# SonarandLEDBoard.net
KiCad netlist of a schematic drawn in EAGLE
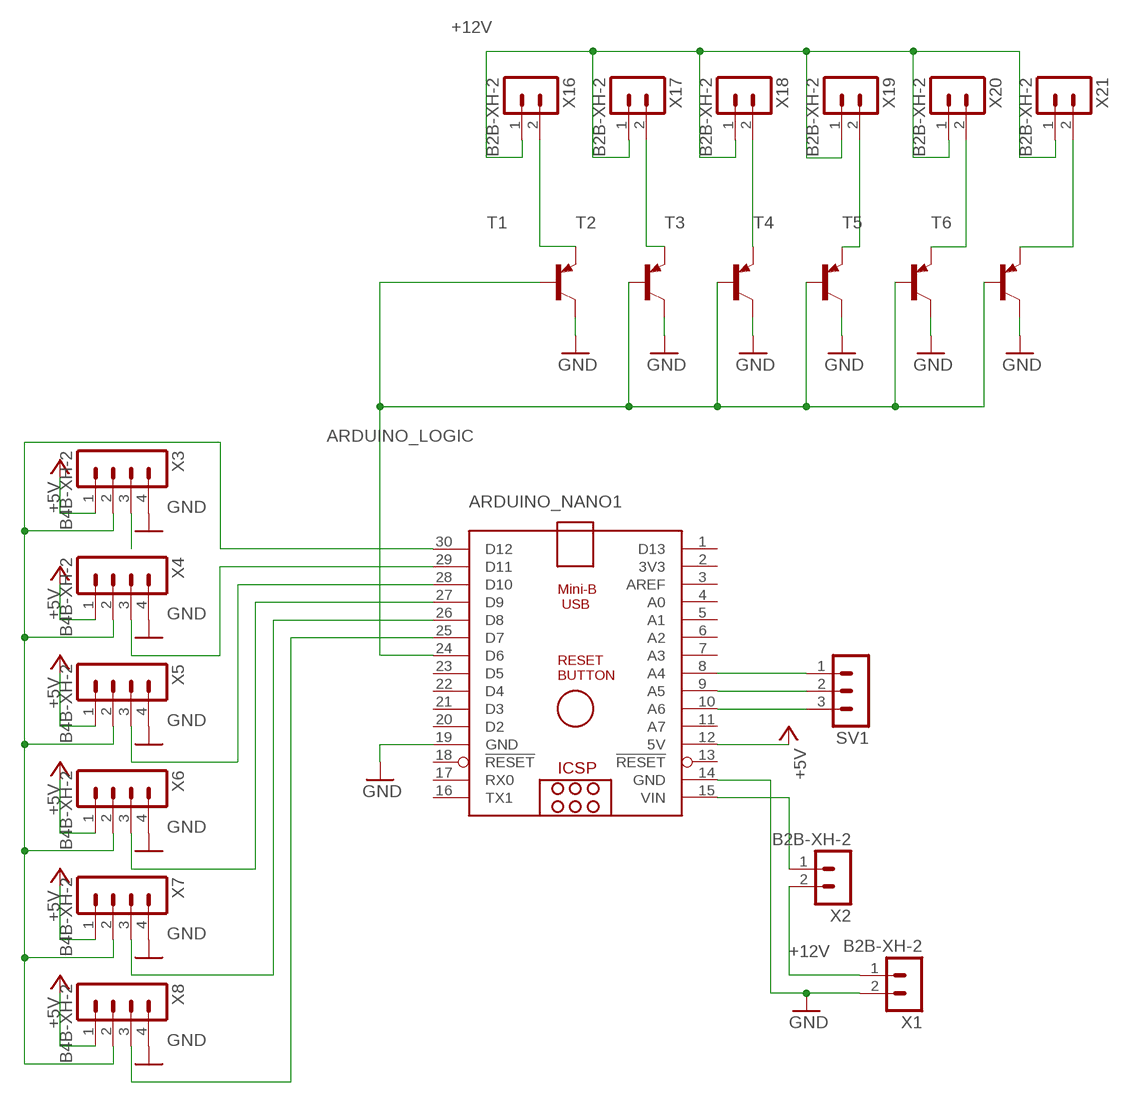
[diagram p0: schematic, sheet 1]

(export (version "E")
  (design (tool "Eeschema 10.0.6"))
  (components
    (comp (ref "ARDUINO_NANO1")
      (value "ARDUINO_NANO")
      (footprint "eagle-import:ARDUINO_NANO")
      (libsource (lib "eagle-import") (part "ARDUINO_NANO"))
    )
    (comp (ref "SV1")
      (value "MA03-1")
      (footprint "eagle-import:MA03-1")
      (libsource (lib "eagle-import") (part "MA03-1"))
    )
    (comp (ref "T1")
      (value "-PNP-TOP3V")
      (footprint "eagle-import:TOP3V")
      (libsource (lib "eagle-import") (part "-PNP-TOP3V"))
    )
    (comp (ref "T2")
      (value "-PNP-TOP3V")
      (footprint "eagle-import:TOP3V")
      (libsource (lib "eagle-import") (part "-PNP-TOP3V"))
    )
    (comp (ref "T3")
      (value "-PNP-TOP3V")
      (footprint "eagle-import:TOP3V")
      (libsource (lib "eagle-import") (part "-PNP-TOP3V"))
    )
    (comp (ref "T4")
      (value "-PNP-TOP3V")
      (footprint "eagle-import:TOP3V")
      (libsource (lib "eagle-import") (part "-PNP-TOP3V"))
    )
    (comp (ref "T5")
      (value "-PNP-TOP3V")
      (footprint "eagle-import:TOP3V")
      (libsource (lib "eagle-import") (part "-PNP-TOP3V"))
    )
    (comp (ref "T6")
      (value "-PNP-TOP3V")
      (footprint "eagle-import:TOP3V")
      (libsource (lib "eagle-import") (part "-PNP-TOP3V"))
    )
    (comp (ref "X1")
      (value "B2B-XH-2")
      (footprint "eagle-import:B2B-XH-A")
      (libsource (lib "eagle-import") (part "B2B-XH-2"))
    )
    (comp (ref "X2")
      (value "B2B-XH-2")
      (footprint "eagle-import:B2B-XH-A")
      (libsource (lib "eagle-import") (part "B2B-XH-2"))
    )
    (comp (ref "X3")
      (value "B4B-XH-2")
      (footprint "eagle-import:B4B-XH-A")
      (libsource (lib "eagle-import") (part "B4B-XH-2"))
    )
    (comp (ref "X4")
      (value "B4B-XH-2")
      (footprint "eagle-import:B4B-XH-A")
      (libsource (lib "eagle-import") (part "B4B-XH-2"))
    )
    (comp (ref "X5")
      (value "B4B-XH-2")
      (footprint "eagle-import:B4B-XH-A")
      (libsource (lib "eagle-import") (part "B4B-XH-2"))
    )
    (comp (ref "X6")
      (value "B4B-XH-2")
      (footprint "eagle-import:B4B-XH-A")
      (libsource (lib "eagle-import") (part "B4B-XH-2"))
    )
    (comp (ref "X7")
      (value "B4B-XH-2")
      (footprint "eagle-import:B4B-XH-A")
      (libsource (lib "eagle-import") (part "B4B-XH-2"))
    )
    (comp (ref "X8")
      (value "B4B-XH-2")
      (footprint "eagle-import:B4B-XH-A")
      (libsource (lib "eagle-import") (part "B4B-XH-2"))
    )
    (comp (ref "X16")
      (value "B2B-XH-2")
      (footprint "eagle-import:B2B-XH-A")
      (libsource (lib "eagle-import") (part "B2B-XH-2"))
    )
    (comp (ref "X17")
      (value "B2B-XH-2")
      (footprint "eagle-import:B2B-XH-A")
      (libsource (lib "eagle-import") (part "B2B-XH-2"))
    )
    (comp (ref "X18")
      (value "B2B-XH-2")
      (footprint "eagle-import:B2B-XH-A")
      (libsource (lib "eagle-import") (part "B2B-XH-2"))
    )
    (comp (ref "X19")
      (value "B2B-XH-2")
      (footprint "eagle-import:B2B-XH-A")
      (libsource (lib "eagle-import") (part "B2B-XH-2"))
    )
    (comp (ref "X20")
      (value "B2B-XH-2")
      (footprint "eagle-import:B2B-XH-A")
      (libsource (lib "eagle-import") (part "B2B-XH-2"))
    )
    (comp (ref "X21")
      (value "B2B-XH-2")
      (footprint "eagle-import:B2B-XH-A")
      (libsource (lib "eagle-import") (part "B2B-XH-2"))
    )
  )
  (nets
    (net (code "1") (name "+5V") (class "Default")
      (node (ref "ARDUINO_NANO1") (pin "12") (pinfunction "5V_12") (pintype "power_in"))
      (node (ref "X3") (pin "1") (pinfunction "1_1") (pintype "passive"))
      (node (ref "X4") (pin "1") (pinfunction "1_1") (pintype "passive"))
      (node (ref "X5") (pin "1") (pinfunction "1_1") (pintype "passive"))
      (node (ref "X6") (pin "1") (pinfunction "1_1") (pintype "passive"))
      (node (ref "X7") (pin "1") (pinfunction "1_1") (pintype "passive"))
      (node (ref "X8") (pin "1") (pinfunction "1_1") (pintype "passive"))
    )
    (net (code "2") (name "/+12V") (class "Default")
      (node (ref "X1") (pin "1") (pinfunction "1_1") (pintype "passive"))
      (node (ref "X16") (pin "1") (pinfunction "1_1") (pintype "passive"))
      (node (ref "X17") (pin "1") (pinfunction "1_1") (pintype "passive"))
      (node (ref "X18") (pin "1") (pinfunction "1_1") (pintype "passive"))
      (node (ref "X19") (pin "1") (pinfunction "1_1") (pintype "passive"))
      (node (ref "X2") (pin "2") (pinfunction "2_2") (pintype "passive"))
      (node (ref "X20") (pin "1") (pinfunction "1_1") (pintype "passive"))
      (node (ref "X21") (pin "1") (pinfunction "1_1") (pintype "passive"))
    )
    (net (code "3") (name "/ARDUINO_LOGIC") (class "Default")
      (node (ref "ARDUINO_NANO1") (pin "24") (pinfunction "D6_24") (pintype "bidirectional"))
      (node (ref "T1") (pin "B") (pinfunction "B_B") (pintype "passive"))
      (node (ref "T2") (pin "B") (pinfunction "B_B") (pintype "passive"))
      (node (ref "T3") (pin "B") (pinfunction "B_B") (pintype "passive"))
      (node (ref "T4") (pin "B") (pinfunction "B_B") (pintype "passive"))
      (node (ref "T5") (pin "B") (pinfunction "B_B") (pintype "passive"))
      (node (ref "T6") (pin "B") (pinfunction "B_B") (pintype "passive"))
    )
    (net (code "4") (name "GND") (class "Default")
      (node (ref "ARDUINO_NANO1") (pin "14") (pinfunction "GND_14") (pintype "power_in"))
      (node (ref "ARDUINO_NANO1") (pin "19") (pinfunction "GND_19") (pintype "power_in"))
      (node (ref "T1") (pin "C") (pinfunction "C_C") (pintype "passive"))
      (node (ref "T2") (pin "C") (pinfunction "C_C") (pintype "passive"))
      (node (ref "T3") (pin "C") (pinfunction "C_C") (pintype "passive"))
      (node (ref "T4") (pin "C") (pinfunction "C_C") (pintype "passive"))
      (node (ref "T5") (pin "C") (pinfunction "C_C") (pintype "passive"))
      (node (ref "T6") (pin "C") (pinfunction "C_C") (pintype "passive"))
      (node (ref "X1") (pin "2") (pinfunction "2_2") (pintype "passive"))
      (node (ref "X3") (pin "4") (pinfunction "4_4") (pintype "passive"))
      (node (ref "X4") (pin "4") (pinfunction "4_4") (pintype "passive"))
      (node (ref "X5") (pin "4") (pinfunction "4_4") (pintype "passive"))
      (node (ref "X6") (pin "4") (pinfunction "4_4") (pintype "passive"))
      (node (ref "X7") (pin "4") (pinfunction "4_4") (pintype "passive"))
      (node (ref "X8") (pin "4") (pinfunction "4_4") (pintype "passive"))
    )
    (net (code "5") (name "Net-(ARDUINO_NANO1-A4)") (class "Default")
      (node (ref "ARDUINO_NANO1") (pin "8") (pinfunction "A4_8") (pintype "bidirectional"))
      (node (ref "SV1") (pin "1") (pinfunction "1_1") (pintype "passive"))
    )
    (net (code "6") (name "Net-(ARDUINO_NANO1-A5)") (class "Default")
      (node (ref "ARDUINO_NANO1") (pin "9") (pinfunction "A5_9") (pintype "bidirectional"))
      (node (ref "SV1") (pin "2") (pinfunction "2_2") (pintype "passive"))
    )
    (net (code "7") (name "Net-(ARDUINO_NANO1-A6)") (class "Default")
      (node (ref "ARDUINO_NANO1") (pin "10") (pinfunction "A6_10") (pintype "bidirectional"))
      (node (ref "SV1") (pin "3") (pinfunction "3_3") (pintype "passive"))
    )
    (net (code "8") (name "Net-(ARDUINO_NANO1-D7)") (class "Default")
      (node (ref "ARDUINO_NANO1") (pin "25") (pinfunction "D7_25") (pintype "bidirectional"))
      (node (ref "X8") (pin "3") (pinfunction "3_3") (pintype "passive"))
    )
    (net (code "9") (name "Net-(ARDUINO_NANO1-D8)") (class "Default")
      (node (ref "ARDUINO_NANO1") (pin "26") (pinfunction "D8_26") (pintype "bidirectional"))
      (node (ref "X7") (pin "3") (pinfunction "3_3") (pintype "passive"))
    )
    (net (code "10") (name "Net-(ARDUINO_NANO1-D9)") (class "Default")
      (node (ref "ARDUINO_NANO1") (pin "27") (pinfunction "D9_27") (pintype "bidirectional"))
      (node (ref "X6") (pin "3") (pinfunction "3_3") (pintype "passive"))
    )
    (net (code "11") (name "Net-(ARDUINO_NANO1-D10)") (class "Default")
      (node (ref "ARDUINO_NANO1") (pin "28") (pinfunction "D10_28") (pintype "bidirectional"))
      (node (ref "X5") (pin "3") (pinfunction "3_3") (pintype "passive"))
    )
    (net (code "12") (name "Net-(ARDUINO_NANO1-D11)") (class "Default")
      (node (ref "ARDUINO_NANO1") (pin "29") (pinfunction "D11_29") (pintype "bidirectional"))
      (node (ref "X4") (pin "3") (pinfunction "3_3") (pintype "passive"))
    )
    (net (code "13") (name "Net-(ARDUINO_NANO1-D12)") (class "Default")
      (node (ref "ARDUINO_NANO1") (pin "30") (pinfunction "D12_30") (pintype "bidirectional"))
      (node (ref "X3") (pin "2") (pinfunction "2_2") (pintype "passive"))
      (node (ref "X4") (pin "2") (pinfunction "2_2") (pintype "passive"))
      (node (ref "X5") (pin "2") (pinfunction "2_2") (pintype "passive"))
      (node (ref "X6") (pin "2") (pinfunction "2_2") (pintype "passive"))
      (node (ref "X7") (pin "2") (pinfunction "2_2") (pintype "passive"))
      (node (ref "X8") (pin "2") (pinfunction "2_2") (pintype "passive"))
    )
    (net (code "14") (name "Net-(ARDUINO_NANO1-VIN)") (class "Default")
      (node (ref "ARDUINO_NANO1") (pin "15") (pinfunction "VIN_15") (pintype "power_in"))
      (node (ref "X2") (pin "1") (pinfunction "1_1") (pintype "passive"))
    )
    (net (code "15") (name "Net-(T1-PadE)") (class "Default")
      (node (ref "T1") (pin "E") (pinfunction "E_E") (pintype "passive"))
      (node (ref "X16") (pin "2") (pinfunction "2_2") (pintype "passive"))
    )
    (net (code "16") (name "Net-(T2-PadE)") (class "Default")
      (node (ref "T2") (pin "E") (pinfunction "E_E") (pintype "passive"))
      (node (ref "X17") (pin "2") (pinfunction "2_2") (pintype "passive"))
    )
    (net (code "17") (name "Net-(T3-PadE)") (class "Default")
      (node (ref "T3") (pin "E") (pinfunction "E_E") (pintype "passive"))
      (node (ref "X18") (pin "2") (pinfunction "2_2") (pintype "passive"))
    )
    (net (code "18") (name "Net-(T4-PadE)") (class "Default")
      (node (ref "T4") (pin "E") (pinfunction "E_E") (pintype "passive"))
      (node (ref "X19") (pin "2") (pinfunction "2_2") (pintype "passive"))
    )
    (net (code "19") (name "Net-(T5-PadE)") (class "Default")
      (node (ref "T5") (pin "E") (pinfunction "E_E") (pintype "passive"))
      (node (ref "X20") (pin "2") (pinfunction "2_2") (pintype "passive"))
    )
    (net (code "20") (name "Net-(T6-PadE)") (class "Default")
      (node (ref "T6") (pin "E") (pinfunction "E_E") (pintype "passive"))
      (node (ref "X21") (pin "2") (pinfunction "2_2") (pintype "passive"))
    )
    (net (code "21") (name "unconnected-(ARDUINO_NANO1-3V3-Pad2)") (class "Default")
      (node (ref "ARDUINO_NANO1") (pin "2") (pinfunction "3V3_2") (pintype "output"))
    )
    (net (code "22") (name "unconnected-(ARDUINO_NANO1-A0-Pad4)") (class "Default")
      (node (ref "ARDUINO_NANO1") (pin "4") (pinfunction "A0_4") (pintype "bidirectional"))
    )
    (net (code "23") (name "unconnected-(ARDUINO_NANO1-A1-Pad5)") (class "Default")
      (node (ref "ARDUINO_NANO1") (pin "5") (pinfunction "A1_5") (pintype "bidirectional"))
    )
    (net (code "24") (name "unconnected-(ARDUINO_NANO1-A2-Pad6)") (class "Default")
      (node (ref "ARDUINO_NANO1") (pin "6") (pinfunction "A2_6") (pintype "bidirectional"))
    )
    (net (code "25") (name "unconnected-(ARDUINO_NANO1-A3-Pad7)") (class "Default")
      (node (ref "ARDUINO_NANO1") (pin "7") (pinfunction "A3_7") (pintype "bidirectional"))
    )
    (net (code "26") (name "unconnected-(ARDUINO_NANO1-A7-Pad11)") (class "Default")
      (node (ref "ARDUINO_NANO1") (pin "11") (pinfunction "A7_11") (pintype "bidirectional"))
    )
    (net (code "27") (name "unconnected-(ARDUINO_NANO1-AREF-Pad3)") (class "Default")
      (node (ref "ARDUINO_NANO1") (pin "3") (pinfunction "AREF_3") (pintype "input"))
    )
    (net (code "28") (name "unconnected-(ARDUINO_NANO1-D2-Pad20)") (class "Default")
      (node (ref "ARDUINO_NANO1") (pin "20") (pinfunction "D2_20") (pintype "bidirectional"))
    )
    (net (code "29") (name "unconnected-(ARDUINO_NANO1-D3-Pad21)") (class "Default")
      (node (ref "ARDUINO_NANO1") (pin "21") (pinfunction "D3_21") (pintype "bidirectional"))
    )
    (net (code "30") (name "unconnected-(ARDUINO_NANO1-D4-Pad22)") (class "Default")
      (node (ref "ARDUINO_NANO1") (pin "22") (pinfunction "D4_22") (pintype "bidirectional"))
    )
    (net (code "31") (name "unconnected-(ARDUINO_NANO1-D5-Pad23)") (class "Default")
      (node (ref "ARDUINO_NANO1") (pin "23") (pinfunction "D5_23") (pintype "bidirectional"))
    )
    (net (code "32") (name "unconnected-(ARDUINO_NANO1-D13-Pad1)") (class "Default")
      (node (ref "ARDUINO_NANO1") (pin "1") (pinfunction "D13_1") (pintype "bidirectional"))
    )
    (net (code "33") (name "unconnected-(ARDUINO_NANO1-RX0-Pad17)") (class "Default")
      (node (ref "ARDUINO_NANO1") (pin "17") (pinfunction "RX0_17") (pintype "bidirectional"))
    )
    (net (code "34") (name "unconnected-(ARDUINO_NANO1-TX1-Pad16)") (class "Default")
      (node (ref "ARDUINO_NANO1") (pin "16") (pinfunction "TX1_16") (pintype "bidirectional"))
    )
    (net (code "35") (name "unconnected-(ARDUINO_NANO1-~{RESET}-Pad13)") (class "Default")
      (node (ref "ARDUINO_NANO1") (pin "13") (pinfunction "~{RESET}_13") (pintype "input"))
    )
    (net (code "36") (name "unconnected-(ARDUINO_NANO1-~{RESET}-Pad18)") (class "Default")
      (node (ref "ARDUINO_NANO1") (pin "18") (pinfunction "~{RESET}_18") (pintype "input"))
    )
    (net (code "37") (name "unconnected-(X3-Pad3)") (class "Default")
      (node (ref "X3") (pin "3") (pinfunction "3_3") (pintype "passive"))
    )
  )
)
